# modFOC-IO.net
KiCad netlist of a schematic drawn in Altium Designer
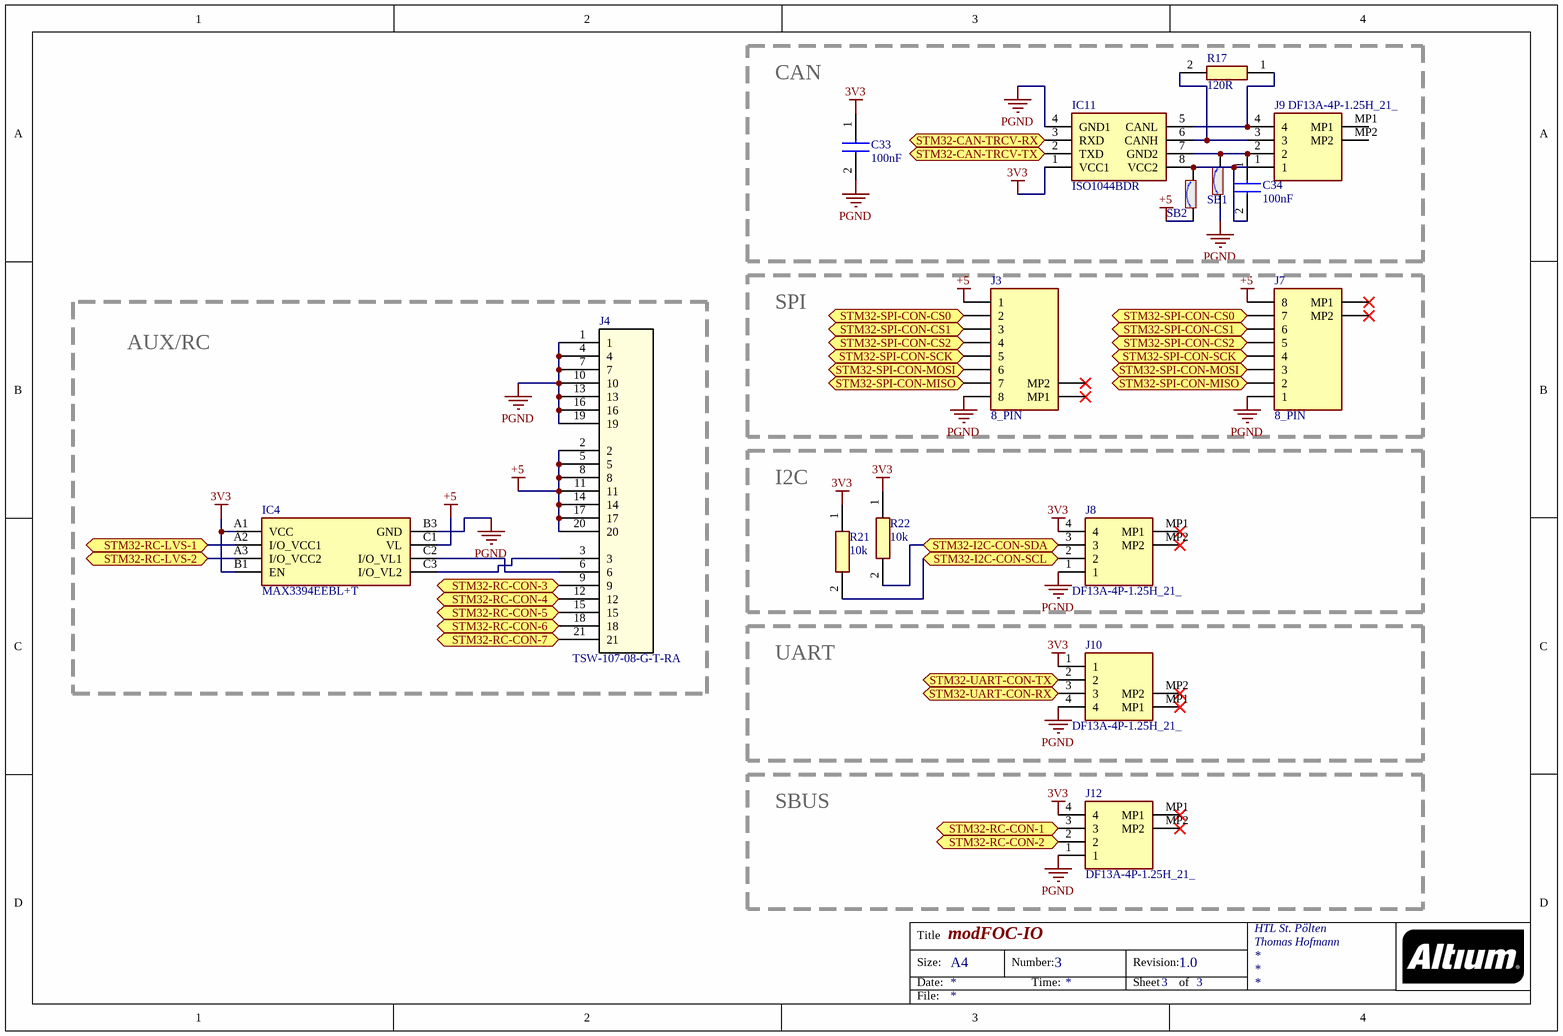
[diagram p0: modFOC-IO.SchDoc]

(export (version "E")
  (design (tool "Eeschema 10.0.6"))
  (components
    (comp (ref "C33")
      (value "100nF")
      (footprint "RcMPPTLib:CAPC1608X97N")
      (description "Capacitor")
      (fields
        (field (name "MANUFACTURER_PART_NUMBER") "VJ0603Y104JXJAC")
        (field (name "MOUSER PART NUMBER") "77-VJ0603Y104JXJAC")
      )
      (libsource (lib "*") (part "VJ0603Y104JXJAC"))
    )
    (comp (ref "C34")
      (value "100nF")
      (footprint "RcMPPTLib:CAPC1608X97N")
      (description "Capacitor")
      (fields
        (field (name "MANUFACTURER_PART_NUMBER") "VJ0603Y104JXJAC")
        (field (name "MOUSER PART NUMBER") "77-VJ0603Y104JXJAC")
      )
      (libsource (lib "*") (part "VJ0603Y104JXJAC"))
    )
    (comp (ref "IC4")
      (value "MAX3394EEBL+T")
      (footprint "RcMPPTLib:BGA8C50P3X3_160X160X67")
      (description "Integrated Circuit")
      (fields (field (name "MOUSER PART NUMBER") "700-MAX3394EEBLT"))
      (libsource (lib "*") (part "MAX3394EEBL+T"))
    )
    (comp (ref "IC11")
      (value "ISO1044BDR")
      (footprint "RcMPPTLib:SOIC127P600X175-8N")
      (description "Integrated Circuit")
      (fields (field (name "MOUSER PART NUMBER") "595-ISO1044BDR"))
      (libsource (lib "*") (part "ISO1044BDR"))
    )
    (comp (ref "J3")
      (value "8_PIN")
      (footprint "DF13A8P125H21")
      (description "Connector")
      (fields
        (field (name "MANUFACTURER_PART_NUMBER") "DF13A-8P-1.25H(21)")
        (field (name "MOUSER PART NUMBER") "798-DF13A8P125H21")
      )
      (libsource (lib "Schlib1") (part "DF13A-8P-1.25H_21_"))
    )
    (comp (ref "J4")
      (value "TSW-107-08-G-T-RA")
      (footprint "TSW-107-08-T-T-RA_SAI")
      (description "No Description Available")
      (fields (field (name "COPYRIGHT") "Copyright (C) 2018 Accelerated Designs. All rights reserved"))
      (libsource (lib "RcMPPTLib") (part "TSW-107-08-G-T-RA"))
    )
    (comp (ref "J7")
      (value "8_PIN")
      (footprint "DF13A8P125H21")
      (description "Connector")
      (fields
        (field (name "MANUFACTURER_PART_NUMBER") "DF13A-8P-1.25H(21)")
        (field (name "MOUSER PART NUMBER") "798-DF13A8P125H21")
      )
      (libsource (lib "") (part "DF13A-8P-1.25H_21__1"))
    )
    (comp (ref "J8")
      (value "DF13A-4P-1.25H_21_")
      (footprint "RcMPPTLib:DF13A4P125H21")
      (description "Connector")
      (fields
        (field (name "MANUFACTURER_PART_NUMBER") "DF13A-4P-1.25H(21)")
        (field (name "MOUSER PART NUMBER") "798-DF13A4P125H21")
      )
      (libsource (lib "") (part "DF13A-4P-1.25H_21__1"))
    )
    (comp (ref "J9")
      (value "DF13A-4P-1.25H_21_")
      (footprint "RcMPPTLib:DF13A4P125H21")
      (description "Connector")
      (fields
        (field (name "MANUFACTURER_PART_NUMBER") "DF13A-4P-1.25H(21)")
        (field (name "MOUSER PART NUMBER") "798-DF13A4P125H21")
      )
      (libsource (lib "") (part "DF13A-4P-1.25H_21__1"))
    )
    (comp (ref "J10")
      (value "DF13A-4P-1.25H_21_")
      (footprint "RcMPPTLib:DF13A4P125H21")
      (description "Connector")
      (fields
        (field (name "MANUFACTURER_PART_NUMBER") "DF13A-4P-1.25H(21)")
        (field (name "MOUSER PART NUMBER") "798-DF13A4P125H21")
      )
      (libsource (lib "RcMPPTLib") (part "DF13A-4P-1.25H_21_"))
    )
    (comp (ref "J12")
      (value "DF13A-4P-1.25H_21_")
      (footprint "RcMPPTLib:DF13A4P125H21")
      (description "Connector")
      (fields
        (field (name "MANUFACTURER_PART_NUMBER") "DF13A-4P-1.25H(21)")
        (field (name "MOUSER PART NUMBER") "798-DF13A4P125H21")
      )
      (libsource (lib "") (part "DF13A-4P-1.25H_21__1"))
    )
    (comp (ref "R17")
      (value "120R")
      (footprint "RcMPPTLib:RESC1608X55N")
      (description "Resistor")
      (fields (field (name "MANUFACTURER_PART_NUMBER") "ERJPA3J121V"))
      (libsource (lib "*") (part "ERJPA3J121V"))
    )
    (comp (ref "R21")
      (value "10k")
      (footprint "RcMPPTLib:RESC1608X55N")
      (description "Resistor")
      (fields
        (field (name "MANUFACTURER_PART_NUMBER") "MCT06030C1002FP500")
        (field (name "MOUSER PART NUMBER") "594-MCT06030C1002FP5")
      )
      (libsource (lib "RcMPPTLib") (part "MCT06030C1002FP500"))
    )
    (comp (ref "R22")
      (value "10k")
      (footprint "RcMPPTLib:RESC1608X55N")
      (description "Resistor")
      (fields
        (field (name "MANUFACTURER_PART_NUMBER") "MCT06030C1002FP500")
        (field (name "MOUSER PART NUMBER") "594-MCT06030C1002FP5")
      )
      (libsource (lib "RcMPPTLib") (part "MCT06030C1002FP500"))
    )
    (comp (ref "SB1")
      (value "Solder Bridge")
      (footprint "SOLDER-BRIDGE_R0603-0R")
      (fields
        (field (name "INTERNAL_PART_NUMBER") "MCD-00071")
        (field (name "MANUFACTURER_PART_NUMBER") "RC0603JR-070RL")
        (field (name "MANUFACTURER") "YAGEO")
        (field (name "PROVIDED_BY") "SUBCO")
      )
      (libsource (lib "RcMPPTLib") (part "Solder Bridge"))
    )
    (comp (ref "SB2")
      (value "Solder Bridge")
      (footprint "SOLDER-BRIDGE_R0603-0R")
      (fields
        (field (name "INTERNAL_PART_NUMBER") "MCD-00071")
        (field (name "MANUFACTURER_PART_NUMBER") "RC0603JR-070RL")
        (field (name "MANUFACTURER") "YAGEO")
        (field (name "PROVIDED_BY") "SUBCO")
      )
      (libsource (lib "RcMPPTLib") (part "Solder Bridge"))
    )
  )
  (nets
    (net (code "1") (name "+5") (class "Default")
      (node (ref "IC4") (pin "C1") (pinfunction "VL_C1") (pintype "passive"))
      (node (ref "J3") (pin "1") (pinfunction "1_1") (pintype "passive"))
      (node (ref "J4") (pin "11") (pinfunction "11_11") (pintype "passive"))
      (node (ref "J4") (pin "14") (pinfunction "14_14") (pintype "passive"))
      (node (ref "J4") (pin "17") (pinfunction "17_17") (pintype "passive"))
      (node (ref "J4") (pin "2") (pinfunction "2_2") (pintype "passive"))
      (node (ref "J4") (pin "20") (pinfunction "20_20") (pintype "passive"))
      (node (ref "J4") (pin "5") (pinfunction "5_5") (pintype "passive"))
      (node (ref "J4") (pin "8") (pinfunction "8_8") (pintype "passive"))
      (node (ref "J7") (pin "8") (pinfunction "8_8") (pintype "passive"))
      (node (ref "SB2") (pin "1") (pinfunction "1_1") (pintype "passive"))
    )
    (net (code "2") (name "/STM32-CAN-TRCV-RX") (class "Default")
      (node (ref "IC11") (pin "3") (pinfunction "RXD_3") (pintype "passive"))
    )
    (net (code "3") (name "/STM32-CAN-TRCV-TX") (class "Default")
      (node (ref "IC11") (pin "2") (pinfunction "TXD_2") (pintype "passive"))
    )
    (net (code "4") (name "/STM32-I2C-CON-SCL") (class "Default")
      (node (ref "J8") (pin "2") (pinfunction "2_2") (pintype "passive"))
      (node (ref "R21") (pin "2") (pinfunction "2_2") (pintype "passive"))
    )
    (net (code "5") (name "/STM32-I2C-CON-SDA") (class "Default")
      (node (ref "J8") (pin "3") (pinfunction "3_3") (pintype "passive"))
      (node (ref "R22") (pin "2") (pinfunction "2_2") (pintype "passive"))
    )
    (net (code "6") (name "/STM32-RC-CON-1") (class "Default")
      (node (ref "J12") (pin "3") (pinfunction "3_3") (pintype "passive"))
    )
    (net (code "7") (name "/STM32-RC-CON-2") (class "Default")
      (node (ref "J12") (pin "2") (pinfunction "2_2") (pintype "passive"))
    )
    (net (code "8") (name "/STM32-RC-CON-3") (class "Default")
      (node (ref "J4") (pin "9") (pinfunction "9_9") (pintype "passive"))
    )
    (net (code "9") (name "/STM32-RC-CON-4") (class "Default")
      (node (ref "J4") (pin "12") (pinfunction "12_12") (pintype "passive"))
    )
    (net (code "10") (name "/STM32-RC-CON-5") (class "Default")
      (node (ref "J4") (pin "15") (pinfunction "15_15") (pintype "passive"))
    )
    (net (code "11") (name "/STM32-RC-CON-6") (class "Default")
      (node (ref "J4") (pin "18") (pinfunction "18_18") (pintype "passive"))
    )
    (net (code "12") (name "/STM32-RC-CON-7") (class "Default")
      (node (ref "J4") (pin "21") (pinfunction "21_21") (pintype "passive"))
    )
    (net (code "13") (name "/STM32-RC-LVS-1") (class "Default")
      (node (ref "IC4") (pin "A2") (pinfunction "I/O_VCC1_A2") (pintype "passive"))
    )
    (net (code "14") (name "/STM32-RC-LVS-2") (class "Default")
      (node (ref "IC4") (pin "A3") (pinfunction "I/O_VCC2_A3") (pintype "passive"))
    )
    (net (code "15") (name "/STM32-SPI-CON-CS0") (class "Default")
      (node (ref "J3") (pin "2") (pinfunction "2_2") (pintype "passive"))
      (node (ref "J7") (pin "7") (pinfunction "7_7") (pintype "passive"))
    )
    (net (code "16") (name "/STM32-SPI-CON-CS1") (class "Default")
      (node (ref "J3") (pin "3") (pinfunction "3_3") (pintype "passive"))
      (node (ref "J7") (pin "6") (pinfunction "6_6") (pintype "passive"))
    )
    (net (code "17") (name "/STM32-SPI-CON-CS2") (class "Default")
      (node (ref "J3") (pin "4") (pinfunction "4_4") (pintype "passive"))
      (node (ref "J7") (pin "5") (pinfunction "5_5") (pintype "passive"))
    )
    (net (code "18") (name "/STM32-SPI-CON-MISO") (class "Default")
      (node (ref "J3") (pin "7") (pinfunction "7_7") (pintype "passive"))
      (node (ref "J7") (pin "2") (pinfunction "2_2") (pintype "passive"))
    )
    (net (code "19") (name "/STM32-SPI-CON-MOSI") (class "Default")
      (node (ref "J3") (pin "6") (pinfunction "6_6") (pintype "passive"))
      (node (ref "J7") (pin "3") (pinfunction "3_3") (pintype "passive"))
    )
    (net (code "20") (name "/STM32-SPI-CON-SCK") (class "Default")
      (node (ref "J3") (pin "5") (pinfunction "5_5") (pintype "passive"))
      (node (ref "J7") (pin "4") (pinfunction "4_4") (pintype "passive"))
    )
    (net (code "21") (name "/STM32-UART-CON-RX") (class "Default")
      (node (ref "J10") (pin "3") (pinfunction "3_3") (pintype "passive"))
    )
    (net (code "22") (name "/STM32-UART-CON-TX") (class "Default")
      (node (ref "J10") (pin "2") (pinfunction "2_2") (pintype "passive"))
    )
    (net (code "23") (name "3V3") (class "Default")
      (node (ref "C33") (pin "1") (pinfunction "1_1") (pintype "passive"))
      (node (ref "IC11") (pin "1") (pinfunction "VCC1_1") (pintype "passive"))
      (node (ref "IC4") (pin "A1") (pinfunction "VCC_A1") (pintype "passive"))
      (node (ref "IC4") (pin "B1") (pinfunction "EN_B1") (pintype "passive"))
      (node (ref "J10") (pin "1") (pinfunction "1_1") (pintype "passive"))
      (node (ref "J12") (pin "4") (pinfunction "4_4") (pintype "passive"))
      (node (ref "J8") (pin "4") (pinfunction "4_4") (pintype "passive"))
      (node (ref "R21") (pin "1") (pinfunction "1_1") (pintype "passive"))
      (node (ref "R22") (pin "1") (pinfunction "1_1") (pintype "passive"))
    )
    (net (code "24") (name "Net-(IC4-I{slash}O_VL1)") (class "Default")
      (node (ref "IC4") (pin "C2") (pinfunction "I/O_VL1_C2") (pintype "passive"))
      (node (ref "J4") (pin "6") (pinfunction "6_6") (pintype "passive"))
    )
    (net (code "25") (name "Net-(IC4-I{slash}O_VL2)") (class "Default")
      (node (ref "IC4") (pin "C3") (pinfunction "I/O_VL2_C3") (pintype "passive"))
      (node (ref "J4") (pin "3") (pinfunction "3_3") (pintype "passive"))
    )
    (net (code "26") (name "Net-(IC11-CANH)") (class "Default")
      (node (ref "IC11") (pin "6") (pinfunction "CANH_6") (pintype "passive"))
      (node (ref "J9") (pin "3") (pinfunction "3_3") (pintype "passive"))
      (node (ref "R17") (pin "2") (pinfunction "2_2") (pintype "passive"))
    )
    (net (code "27") (name "Net-(IC11-CANL)") (class "Default")
      (node (ref "IC11") (pin "5") (pinfunction "CANL_5") (pintype "passive"))
      (node (ref "J9") (pin "4") (pinfunction "4_4") (pintype "passive"))
      (node (ref "R17") (pin "1") (pinfunction "1_1") (pintype "passive"))
    )
    (net (code "28") (name "Net-(IC11-GND2)") (class "Default")
      (node (ref "C34") (pin "1") (pinfunction "1_1") (pintype "passive"))
      (node (ref "IC11") (pin "7") (pinfunction "GND2_7") (pintype "passive"))
      (node (ref "J9") (pin "2") (pinfunction "2_2") (pintype "passive"))
      (node (ref "SB1") (pin "2") (pinfunction "2_2") (pintype "passive"))
    )
    (net (code "29") (name "Net-(IC11-VCC2)") (class "Default")
      (node (ref "C34") (pin "2") (pinfunction "2_2") (pintype "passive"))
      (node (ref "IC11") (pin "8") (pinfunction "VCC2_8") (pintype "passive"))
      (node (ref "J9") (pin "1") (pinfunction "1_1") (pintype "passive"))
      (node (ref "SB2") (pin "2") (pinfunction "2_2") (pintype "passive"))
    )
    (net (code "30") (name "PGND") (class "Default")
      (node (ref "C33") (pin "2") (pinfunction "2_2") (pintype "passive"))
      (node (ref "IC11") (pin "4") (pinfunction "GND1_4") (pintype "passive"))
      (node (ref "IC4") (pin "B3") (pinfunction "GND_B3") (pintype "passive"))
      (node (ref "J10") (pin "4") (pinfunction "4_4") (pintype "passive"))
      (node (ref "J12") (pin "1") (pinfunction "1_1") (pintype "passive"))
      (node (ref "J3") (pin "8") (pinfunction "8_8") (pintype "passive"))
      (node (ref "J4") (pin "1") (pinfunction "1_1") (pintype "passive"))
      (node (ref "J4") (pin "10") (pinfunction "10_10") (pintype "passive"))
      (node (ref "J4") (pin "13") (pinfunction "13_13") (pintype "passive"))
      (node (ref "J4") (pin "16") (pinfunction "16_16") (pintype "passive"))
      (node (ref "J4") (pin "19") (pinfunction "19_19") (pintype "passive"))
      (node (ref "J4") (pin "4") (pinfunction "4_4") (pintype "passive"))
      (node (ref "J4") (pin "7") (pinfunction "7_7") (pintype "passive"))
      (node (ref "J7") (pin "1") (pinfunction "1_1") (pintype "passive"))
      (node (ref "J8") (pin "1") (pinfunction "1_1") (pintype "passive"))
      (node (ref "SB1") (pin "1") (pinfunction "1_1") (pintype "passive"))
    )
    (net (code "31") (name "unconnected-(J3-PadMP1)") (class "Default")
      (node (ref "J3") (pin "MP1") (pinfunction "MP1_MP1") (pintype "passive+no_connect"))
    )
    (net (code "32") (name "unconnected-(J3-PadMP2)") (class "Default")
      (node (ref "J3") (pin "MP2") (pinfunction "MP2_MP2") (pintype "passive+no_connect"))
    )
    (net (code "33") (name "unconnected-(J7-PadMP1)") (class "Default")
      (node (ref "J7") (pin "MP1") (pinfunction "MP1_MP1") (pintype "passive+no_connect"))
    )
    (net (code "34") (name "unconnected-(J7-PadMP2)") (class "Default")
      (node (ref "J7") (pin "MP2") (pinfunction "MP2_MP2") (pintype "passive+no_connect"))
    )
    (net (code "35") (name "unconnected-(J8-PadMP1)") (class "Default")
      (node (ref "J8") (pin "MP1") (pinfunction "MP1_MP1") (pintype "passive+no_connect"))
    )
    (net (code "36") (name "unconnected-(J8-PadMP2)") (class "Default")
      (node (ref "J8") (pin "MP2") (pinfunction "MP2_MP2") (pintype "passive+no_connect"))
    )
    (net (code "37") (name "unconnected-(J9-PadMP1)") (class "Default")
      (node (ref "J9") (pin "MP1") (pinfunction "MP1_MP1") (pintype "passive"))
    )
    (net (code "38") (name "unconnected-(J9-PadMP2)") (class "Default")
      (node (ref "J9") (pin "MP2") (pinfunction "MP2_MP2") (pintype "passive"))
    )
    (net (code "39") (name "unconnected-(J10-PadMP1)") (class "Default")
      (node (ref "J10") (pin "MP1") (pinfunction "MP1_MP1") (pintype "passive+no_connect"))
    )
    (net (code "40") (name "unconnected-(J10-PadMP2)") (class "Default")
      (node (ref "J10") (pin "MP2") (pinfunction "MP2_MP2") (pintype "passive+no_connect"))
    )
    (net (code "41") (name "unconnected-(J12-PadMP1)") (class "Default")
      (node (ref "J12") (pin "MP1") (pinfunction "MP1_MP1") (pintype "passive+no_connect"))
    )
    (net (code "42") (name "unconnected-(J12-PadMP2)") (class "Default")
      (node (ref "J12") (pin "MP2") (pinfunction "MP2_MP2") (pintype "passive+no_connect"))
    )
  )
)
